# sch_Camera.net
KiCad netlist of a schematic drawn in Altium Designer
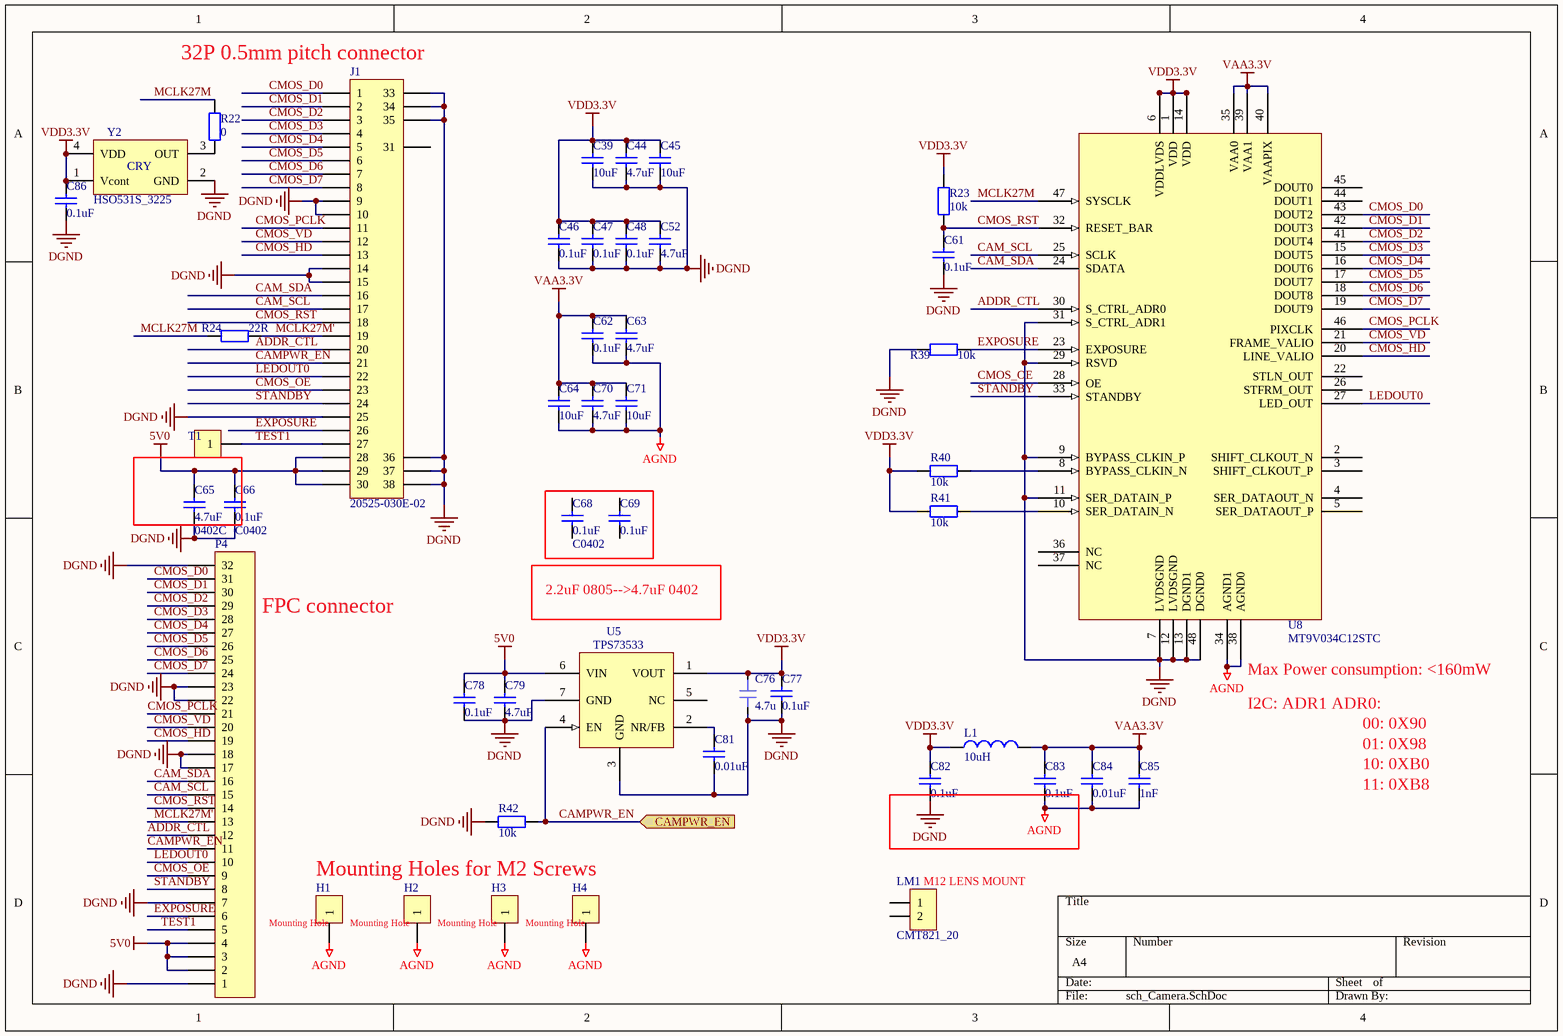
[diagram p0: sch_Camera.SchDoc]

(export (version "E")
  (design (tool "Eeschema 10.0.6"))
  (components
    (comp (ref "C39")
      (value "10uF")
      (footprint "0805C")
      (description "Capacitor")
      (fields (field (name "PUBLISHER") "Altium Limited"))
      (libsource (lib "Miscellaneous Devices") (part "Cap"))
    )
    (comp (ref "C44")
      (value "4.7uF")
      (footprint "0402C")
      (description "Capacitor")
      (fields (field (name "PUBLISHER") "Altium Limited"))
      (libsource (lib "Miscellaneous Devices") (part "Cap"))
    )
    (comp (ref "C45")
      (value "10uF")
      (footprint "0805C")
      (description "Capacitor")
      (fields (field (name "PUBLISHER") "Altium Limited"))
      (libsource (lib "Miscellaneous Devices") (part "Cap"))
    )
    (comp (ref "C46")
      (value "0.1uF")
      (footprint "0402C")
      (description "Capacitor")
      (fields (field (name "PUBLISHER") "Altium Limited"))
      (libsource (lib "Miscellaneous Devices") (part "Cap"))
    )
    (comp (ref "C47")
      (value "0.1uF")
      (footprint "0402C")
      (description "Capacitor")
      (fields (field (name "PUBLISHER") "Altium Limited"))
      (libsource (lib "Miscellaneous Devices") (part "Cap"))
    )
    (comp (ref "C48")
      (value "0.1uF")
      (footprint "0402C")
      (description "Capacitor")
      (fields (field (name "PUBLISHER") "Altium Limited"))
      (libsource (lib "Miscellaneous Devices") (part "Cap"))
    )
    (comp (ref "C52")
      (value "4.7uF")
      (footprint "0402C")
      (description "Capacitor")
      (fields (field (name "PUBLISHER") "Altium Limited"))
      (libsource (lib "Miscellaneous Devices") (part "Cap"))
    )
    (comp (ref "C61")
      (value "0.1uF")
      (footprint "0402C")
      (description "Capacitor")
      (fields (field (name "PUBLISHER") "Altium Limited"))
      (libsource (lib "Miscellaneous Devices") (part "Cap"))
    )
    (comp (ref "C62")
      (value "0.1uF")
      (footprint "0402C")
      (description "Capacitor")
      (fields (field (name "PUBLISHER") "Altium Limited"))
      (libsource (lib "Miscellaneous Devices") (part "Cap"))
    )
    (comp (ref "C63")
      (value "4.7uF")
      (footprint "0402C")
      (description "Capacitor")
      (fields (field (name "PUBLISHER") "Altium Limited"))
      (libsource (lib "Miscellaneous Devices") (part "Cap"))
    )
    (comp (ref "C64")
      (value "10uF")
      (footprint "0805C")
      (description "Capacitor")
      (fields (field (name "PUBLISHER") "Altium Limited"))
      (libsource (lib "Miscellaneous Devices") (part "Cap"))
    )
    (comp (ref "C65")
      (value "4.7uF")
      (footprint "0402C")
      (description "Capacitor")
      (fields (field (name "ALTIUM_VALUE") "0402C") (field (name "PUBLISHER") "Altium Limited"))
      (libsource (lib "Miscellaneous Devices") (part "Cap"))
    )
    (comp (ref "C66")
      (value "0.1uF")
      (footprint "0402C")
      (description "Capacitor")
      (fields (field (name "ALTIUM_VALUE") "C0402") (field (name "PUBLISHER") "Altium Limited"))
      (libsource (lib "Miscellaneous Devices") (part "Cap"))
    )
    (comp (ref "C68")
      (value "0.1uF")
      (footprint "0402C")
      (description "Capacitor")
      (fields (field (name "ALTIUM_VALUE") "C0402") (field (name "PUBLISHER") "Altium Limited"))
      (libsource (lib "Miscellaneous Devices") (part "Cap"))
    )
    (comp (ref "C69")
      (value "0.1uF")
      (footprint "0402C")
      (description "Capacitor")
      (fields (field (name "PUBLISHER") "Altium Limited"))
      (libsource (lib "Miscellaneous Devices") (part "Cap"))
    )
    (comp (ref "C70")
      (value "4.7uF")
      (footprint "0402C")
      (description "Capacitor")
      (fields (field (name "PUBLISHER") "Altium Limited"))
      (libsource (lib "Miscellaneous Devices") (part "Cap"))
    )
    (comp (ref "C71")
      (value "10uF")
      (footprint "0805C")
      (description "Capacitor")
      (fields (field (name "PUBLISHER") "Altium Limited"))
      (libsource (lib "Miscellaneous Devices") (part "Cap"))
    )
    (comp (ref "C76")
      (value "4.7u")
      (footprint "0402C_L")
      (description "CC0402MRX5R5BB475")
      (libsource (lib "V0P1") (part "cap0402"))
    )
    (comp (ref "C77")
      (value "0.1uF")
      (footprint "0402C_L")
      (description "Capacitor")
      (fields (field (name "PUBLISHER") "Altium Limited"))
      (libsource (lib "Miscellaneous Devices") (part "Cap"))
    )
    (comp (ref "C78")
      (value "0.1uF")
      (footprint "0402C")
      (description "Capacitor")
      (fields (field (name "PUBLISHER") "Altium Limited"))
      (libsource (lib "Miscellaneous Devices") (part "Cap"))
    )
    (comp (ref "C79")
      (value "4.7uF")
      (footprint "0402C_L")
      (description "Capacitor")
      (fields (field (name "PUBLISHER") "Altium Limited"))
      (libsource (lib "Miscellaneous Devices") (part "Cap"))
    )
    (comp (ref "C81")
      (value "0.01uF")
      (footprint "0402C_L")
      (description "Capacitor")
      (fields (field (name "PUBLISHER") "Altium Limited"))
      (libsource (lib "Miscellaneous Devices") (part "Cap"))
    )
    (comp (ref "C82")
      (value "0.1uF")
      (footprint "0402C_L")
      (description "Capacitor")
      (fields (field (name "PUBLISHER") "Altium Limited"))
      (libsource (lib "Miscellaneous Devices") (part "Cap"))
    )
    (comp (ref "C83")
      (value "0.1uF")
      (footprint "0402C_L")
      (description "Capacitor")
      (fields (field (name "PUBLISHER") "Altium Limited"))
      (libsource (lib "Miscellaneous Devices") (part "Cap"))
    )
    (comp (ref "C84")
      (value "0.01uF")
      (footprint "0402C_L")
      (description "Capacitor")
      (fields (field (name "PUBLISHER") "Altium Limited"))
      (libsource (lib "Miscellaneous Devices") (part "Cap"))
    )
    (comp (ref "C85")
      (value "1nF")
      (footprint "0402C_L")
      (description "Capacitor")
      (fields (field (name "PUBLISHER") "Altium Limited"))
      (libsource (lib "Miscellaneous Devices") (part "Cap"))
    )
    (comp (ref "C86")
      (value "0.1uF")
      (footprint "0402C")
      (description "Capacitor")
      (fields (field (name "PUBLISHER") "Altium Limited"))
      (libsource (lib "Miscellaneous Devices") (part "Cap"))
    )
    (comp (ref "H1")
      (value "CON1")
      (footprint "PAD_M3_D350_450")
      (description "Connector")
      (libsource (lib "") (part "CON1_1"))
    )
    (comp (ref "H2")
      (value "CON1")
      (footprint "PAD_M3_D350_450")
      (description "Connector")
      (libsource (lib "") (part "CON1_1"))
    )
    (comp (ref "H3")
      (value "CON1")
      (footprint "PAD_M3_D350_450")
      (description "Connector")
      (libsource (lib "") (part "CON1_1"))
    )
    (comp (ref "H4")
      (value "CON1")
      (footprint "PAD_M3_D350_450")
      (description "Connector")
      (libsource (lib "") (part "CON1_1"))
    )
    (comp (ref "J1")
      (value "20525-030E-02")
      (footprint "HSA30_P40L196W42H10_20525")
      (libsource (lib "SZG") (part "20525-030E-02"))
    )
    (comp (ref "L1")
      (value "10uH")
      (footprint "0805R")
      (description "Inductor")
      (libsource (lib "SWUST_ROBOT") (part "Inductor"))
    )
    (comp (ref "LM1")
      (value "CMT821_20")
      (footprint "PAD_M3_D350_450")
      (description "Connector")
      (libsource (lib "SuperSchLib") (part "CON2"))
    )
    (comp (ref "P4")
      (value "Header_32")
      (footprint "HS32A_FPC_P50L2350W480H210")
      (description "Header, 30-Pin, Dual row")
      (fields (field (name "PUBLISHER") "Altium Limited"))
      (libsource (lib "TXW") (part "Header 30X2"))
    )
    (comp (ref "R22")
      (value "0")
      (footprint "0402R")
      (description "Resistor")
      (fields (field (name "Comment") "0R") (field (name "PUBLISHER") "Altium Limited"))
      (libsource (lib "") (part "Resistor_2"))
    )
    (comp (ref "R23")
      (value "10k")
      (footprint "0402R")
      (description "Resistor")
      (fields (field (name "Comment") "10K") (field (name "PUBLISHER") "Altium Limited"))
      (libsource (lib "") (part "Resistor_1"))
    )
    (comp (ref "R24")
      (value "22R")
      (footprint "0402R")
      (description "Resistor")
      (fields (field (name "PUBLISHER") "Altium Limited"))
      (libsource (lib "") (part "Resistor_1"))
    )
    (comp (ref "R39")
      (value "10k")
      (footprint "0402R")
      (description "Resistor")
      (fields (field (name "Comment") "10K") (field (name "PUBLISHER") "Altium Limited"))
      (libsource (lib "SZG") (part "Resistor"))
    )
    (comp (ref "R40")
      (value "10k")
      (footprint "0402R")
      (description "Resistor")
      (fields (field (name "Comment") "10K") (field (name "PUBLISHER") "Altium Limited"))
      (libsource (lib "SZG") (part "Resistor"))
    )
    (comp (ref "R41")
      (value "10k")
      (footprint "0402R")
      (description "Resistor")
      (fields (field (name "Comment") "10K") (field (name "PUBLISHER") "Altium Limited"))
      (libsource (lib "SZG") (part "Resistor"))
    )
    (comp (ref "R42")
      (value "10k")
      (footprint "0402R_L")
      (description "Resistor")
      (fields (field (name "Comment") "10K") (field (name "PUBLISHER") "Altium Limited"))
      (libsource (lib "") (part "Resistor_3"))
    )
    (comp (ref "T1")
      (value "CON1")
      (footprint "PAD_TP_D1.2")
      (description "Connector")
      (libsource (lib "SuperSchLib") (part "CON1"))
    )
    (comp (ref "U5")
      (value "TPS73533")
      (footprint "SON6_P65L21W21H8_DRV")
      (libsource (lib "SZG") (part "TPS73533"))
    )
    (comp (ref "U8")
      (value "MT9V034C12STC")
      (footprint "CLCC48_P80L114W114H23")
      (libsource (lib "TXW") (part "MT9V034"))
    )
    (comp (ref "Y2")
      (value "HSO531S_3225")
      (footprint "XTAL_3225")
      (description "有源晶振")
      (libsource (lib "超集元件库") (part "CRY"))
    )
  )
  (nets
    (net (code "1") (name "/ADDR_CTL") (class "Default")
      (node (ref "J1") (pin "20") (pinfunction "20_20") (pintype "passive"))
      (node (ref "P4") (pin "12") (pinfunction "12_12") (pintype "passive"))
      (node (ref "U8") (pin "30") (pinfunction "S_CTRL_ADR0_30") (pintype "input"))
    )
    (net (code "2") (name "/CAMPWR_EN") (class "Default")
      (node (ref "J1") (pin "21") (pinfunction "21_21") (pintype "passive"))
      (node (ref "P4") (pin "11") (pinfunction "11_11") (pintype "passive"))
      (node (ref "R42") (pin "2") (pinfunction "2_2") (pintype "passive"))
      (node (ref "U5") (pin "4") (pinfunction "EN_4") (pintype "input"))
    )
    (net (code "3") (name "/CAM_SCL") (class "Default")
      (node (ref "J1") (pin "17") (pinfunction "17_17") (pintype "passive"))
      (node (ref "P4") (pin "15") (pinfunction "15_15") (pintype "passive"))
      (node (ref "U8") (pin "25") (pinfunction "SCLK_25") (pintype "input"))
    )
    (net (code "4") (name "/CAM_SDA") (class "Default")
      (node (ref "J1") (pin "16") (pinfunction "16_16") (pintype "passive"))
      (node (ref "P4") (pin "16") (pinfunction "16_16") (pintype "passive"))
      (node (ref "U8") (pin "24") (pinfunction "SDATA_24") (pintype "passive"))
    )
    (net (code "5") (name "/CMOS_D0") (class "Default")
      (node (ref "J1") (pin "1") (pinfunction "1_1") (pintype "passive"))
      (node (ref "P4") (pin "31") (pinfunction "31_31") (pintype "passive"))
      (node (ref "U8") (pin "43") (pinfunction "DOUT2_43") (pintype "passive"))
    )
    (net (code "6") (name "/CMOS_D1") (class "Default")
      (node (ref "J1") (pin "2") (pinfunction "2_2") (pintype "passive"))
      (node (ref "P4") (pin "30") (pinfunction "30_30") (pintype "passive"))
      (node (ref "U8") (pin "42") (pinfunction "DOUT3_42") (pintype "passive"))
    )
    (net (code "7") (name "/CMOS_D2") (class "Default")
      (node (ref "J1") (pin "3") (pinfunction "3_3") (pintype "passive"))
      (node (ref "P4") (pin "29") (pinfunction "29_29") (pintype "passive"))
      (node (ref "U8") (pin "41") (pinfunction "DOUT4_41") (pintype "passive"))
    )
    (net (code "8") (name "/CMOS_D3") (class "Default")
      (node (ref "J1") (pin "4") (pinfunction "4_4") (pintype "passive"))
      (node (ref "P4") (pin "28") (pinfunction "28_28") (pintype "passive"))
      (node (ref "U8") (pin "15") (pinfunction "DOUT5_15") (pintype "passive"))
    )
    (net (code "9") (name "/CMOS_D4") (class "Default")
      (node (ref "J1") (pin "5") (pinfunction "5_5") (pintype "passive"))
      (node (ref "P4") (pin "27") (pinfunction "27_27") (pintype "passive"))
      (node (ref "U8") (pin "16") (pinfunction "DOUT6_16") (pintype "passive"))
    )
    (net (code "10") (name "/CMOS_D5") (class "Default")
      (node (ref "J1") (pin "6") (pinfunction "6_6") (pintype "passive"))
      (node (ref "P4") (pin "26") (pinfunction "26_26") (pintype "passive"))
      (node (ref "U8") (pin "17") (pinfunction "DOUT7_17") (pintype "passive"))
    )
    (net (code "11") (name "/CMOS_D6") (class "Default")
      (node (ref "J1") (pin "7") (pinfunction "7_7") (pintype "passive"))
      (node (ref "P4") (pin "25") (pinfunction "25_25") (pintype "passive"))
      (node (ref "U8") (pin "18") (pinfunction "DOUT8_18") (pintype "passive"))
    )
    (net (code "12") (name "/CMOS_D7") (class "Default")
      (node (ref "J1") (pin "8") (pinfunction "8_8") (pintype "passive"))
      (node (ref "P4") (pin "24") (pinfunction "24_24") (pintype "passive"))
      (node (ref "U8") (pin "19") (pinfunction "DOUT9_19") (pintype "passive"))
    )
    (net (code "13") (name "/CMOS_HD") (class "Default")
      (node (ref "J1") (pin "13") (pinfunction "13_13") (pintype "passive"))
      (node (ref "P4") (pin "19") (pinfunction "19_19") (pintype "passive"))
      (node (ref "U8") (pin "20") (pinfunction "LINE_VALIO_20") (pintype "passive"))
    )
    (net (code "14") (name "/CMOS_OE") (class "Default")
      (node (ref "J1") (pin "23") (pinfunction "23_23") (pintype "passive"))
      (node (ref "P4") (pin "9") (pinfunction "9_9") (pintype "passive"))
      (node (ref "U8") (pin "28") (pinfunction "OE_28") (pintype "input"))
    )
    (net (code "15") (name "/CMOS_PCLK") (class "Default")
      (node (ref "J1") (pin "11") (pinfunction "11_11") (pintype "passive"))
      (node (ref "P4") (pin "21") (pinfunction "21_21") (pintype "passive"))
      (node (ref "U8") (pin "46") (pinfunction "PIXCLK_46") (pintype "passive"))
    )
    (net (code "16") (name "/CMOS_RST") (class "Default")
      (node (ref "C61") (pin "2") (pinfunction "2_2") (pintype "passive"))
      (node (ref "J1") (pin "18") (pinfunction "18_18") (pintype "passive"))
      (node (ref "P4") (pin "14") (pinfunction "14_14") (pintype "passive"))
      (node (ref "R23") (pin "1") (pinfunction "1_1") (pintype "passive"))
      (node (ref "U8") (pin "32") (pinfunction "RESET_BAR_32") (pintype "input"))
    )
    (net (code "17") (name "/CMOS_VD") (class "Default")
      (node (ref "J1") (pin "12") (pinfunction "12_12") (pintype "passive"))
      (node (ref "P4") (pin "20") (pinfunction "20_20") (pintype "passive"))
      (node (ref "U8") (pin "21") (pinfunction "FRAME_VALIO_21") (pintype "passive"))
    )
    (net (code "18") (name "/EXPOSURE") (class "Default")
      (node (ref "J1") (pin "26") (pinfunction "26_26") (pintype "passive"))
      (node (ref "P4") (pin "6") (pinfunction "6_6") (pintype "passive"))
      (node (ref "R39") (pin "1") (pinfunction "1_1") (pintype "passive"))
      (node (ref "U8") (pin "23") (pinfunction "EXPOSURE_23") (pintype "input"))
    )
    (net (code "19") (name "/LEDOUT0") (class "Default")
      (node (ref "J1") (pin "22") (pinfunction "22_22") (pintype "passive"))
      (node (ref "P4") (pin "10") (pinfunction "10_10") (pintype "passive"))
      (node (ref "U8") (pin "27") (pinfunction "LED_OUT_27") (pintype "passive"))
    )
    (net (code "20") (name "/MCLK27M") (class "Default")
      (node (ref "R22") (pin "1") (pinfunction "1_1") (pintype "passive"))
      (node (ref "R24") (pin "1") (pinfunction "1_1") (pintype "passive"))
      (node (ref "U8") (pin "47") (pinfunction "SYSCLK_47") (pintype "input"))
    )
    (net (code "21") (name "/MCLK27M'") (class "Default")
      (node (ref "J1") (pin "19") (pinfunction "19_19") (pintype "passive"))
      (node (ref "P4") (pin "13") (pinfunction "13_13") (pintype "passive"))
      (node (ref "R24") (pin "2") (pinfunction "2_2") (pintype "passive"))
    )
    (net (code "22") (name "/STANDBY") (class "Default")
      (node (ref "J1") (pin "24") (pinfunction "24_24") (pintype "passive"))
      (node (ref "P4") (pin "8") (pinfunction "8_8") (pintype "passive"))
      (node (ref "U8") (pin "33") (pinfunction "STANDBY_33") (pintype "input"))
    )
    (net (code "23") (name "/TEST1") (class "Default")
      (node (ref "J1") (pin "27") (pinfunction "27_27") (pintype "passive"))
      (node (ref "P4") (pin "5") (pinfunction "5_5") (pintype "passive"))
      (node (ref "T1") (pin "1") (pinfunction "1_1") (pintype "passive"))
    )
    (net (code "24") (name "5V0") (class "Default")
      (node (ref "C65") (pin "2") (pinfunction "2_2") (pintype "passive"))
      (node (ref "C66") (pin "2") (pinfunction "2_2") (pintype "passive"))
      (node (ref "C78") (pin "2") (pinfunction "2_2") (pintype "passive"))
      (node (ref "C79") (pin "2") (pinfunction "2_2") (pintype "passive"))
      (node (ref "J1") (pin "28") (pinfunction "28_28") (pintype "passive"))
      (node (ref "J1") (pin "29") (pinfunction "29_29") (pintype "passive"))
      (node (ref "J1") (pin "30") (pinfunction "30_30") (pintype "passive"))
      (node (ref "P4") (pin "2") (pinfunction "2_2") (pintype "passive"))
      (node (ref "P4") (pin "3") (pinfunction "3_3") (pintype "passive"))
      (node (ref "P4") (pin "4") (pinfunction "4_4") (pintype "passive"))
      (node (ref "U5") (pin "6") (pinfunction "VIN_6") (pintype "passive"))
    )
    (net (code "25") (name "AGND") (class "Default")
      (node (ref "C62") (pin "1") (pinfunction "1_1") (pintype "passive"))
      (node (ref "C63") (pin "1") (pinfunction "1_1") (pintype "passive"))
      (node (ref "C64") (pin "1") (pinfunction "1_1") (pintype "passive"))
      (node (ref "C70") (pin "1") (pinfunction "1_1") (pintype "passive"))
      (node (ref "C71") (pin "1") (pinfunction "1_1") (pintype "passive"))
      (node (ref "C83") (pin "1") (pinfunction "1_1") (pintype "passive"))
      (node (ref "C84") (pin "1") (pinfunction "1_1") (pintype "passive"))
      (node (ref "C85") (pin "1") (pinfunction "1_1") (pintype "passive"))
      (node (ref "H1") (pin "1") (pinfunction "1_1") (pintype "passive"))
      (node (ref "H2") (pin "1") (pinfunction "1_1") (pintype "passive"))
      (node (ref "H3") (pin "1") (pinfunction "1_1") (pintype "passive"))
      (node (ref "H4") (pin "1") (pinfunction "1_1") (pintype "passive"))
      (node (ref "U8") (pin "34") (pinfunction "AGND1_34") (pintype "power_in"))
      (node (ref "U8") (pin "38") (pinfunction "AGND0_38") (pintype "power_in"))
    )
    (net (code "26") (name "DGND") (class "Default")
      (node (ref "C39") (pin "1") (pinfunction "1_1") (pintype "passive"))
      (node (ref "C44") (pin "1") (pinfunction "1_1") (pintype "passive"))
      (node (ref "C45") (pin "1") (pinfunction "1_1") (pintype "passive"))
      (node (ref "C46") (pin "1") (pinfunction "1_1") (pintype "passive"))
      (node (ref "C47") (pin "1") (pinfunction "1_1") (pintype "passive"))
      (node (ref "C48") (pin "1") (pinfunction "1_1") (pintype "passive"))
      (node (ref "C52") (pin "1") (pinfunction "1_1") (pintype "passive"))
      (node (ref "C61") (pin "1") (pinfunction "1_1") (pintype "passive"))
      (node (ref "C65") (pin "1") (pinfunction "1_1") (pintype "passive"))
      (node (ref "C66") (pin "1") (pinfunction "1_1") (pintype "passive"))
      (node (ref "C76") (pin "2") (pinfunction "2_2") (pintype "passive"))
      (node (ref "C77") (pin "1") (pinfunction "1_1") (pintype "passive"))
      (node (ref "C78") (pin "1") (pinfunction "1_1") (pintype "passive"))
      (node (ref "C79") (pin "1") (pinfunction "1_1") (pintype "passive"))
      (node (ref "C81") (pin "1") (pinfunction "1_1") (pintype "passive"))
      (node (ref "C82") (pin "1") (pinfunction "1_1") (pintype "passive"))
      (node (ref "C86") (pin "1") (pinfunction "1_1") (pintype "passive"))
      (node (ref "J1") (pin "10") (pinfunction "10_10") (pintype "passive"))
      (node (ref "J1") (pin "14") (pinfunction "14_14") (pintype "passive"))
      (node (ref "J1") (pin "15") (pinfunction "15_15") (pintype "passive"))
      (node (ref "J1") (pin "25") (pinfunction "25_25") (pintype "passive"))
      (node (ref "J1") (pin "33") (pinfunction "33_33") (pintype "passive"))
      (node (ref "J1") (pin "34") (pinfunction "34_34") (pintype "passive"))
      (node (ref "J1") (pin "35") (pinfunction "35_35") (pintype "passive"))
      (node (ref "J1") (pin "36") (pinfunction "36_36") (pintype "passive"))
      (node (ref "J1") (pin "37") (pinfunction "37_37") (pintype "passive"))
      (node (ref "J1") (pin "38") (pinfunction "38_38") (pintype "passive"))
      (node (ref "J1") (pin "9") (pinfunction "9_9") (pintype "passive"))
      (node (ref "P4") (pin "1") (pinfunction "1_1") (pintype "passive"))
      (node (ref "P4") (pin "17") (pinfunction "17_17") (pintype "passive"))
      (node (ref "P4") (pin "18") (pinfunction "18_18") (pintype "passive"))
      (node (ref "P4") (pin "22") (pinfunction "22_22") (pintype "passive"))
      (node (ref "P4") (pin "23") (pinfunction "23_23") (pintype "passive"))
      (node (ref "P4") (pin "32") (pinfunction "32_32") (pintype "passive"))
      (node (ref "P4") (pin "7") (pinfunction "7_7") (pintype "passive"))
      (node (ref "R39") (pin "2") (pinfunction "2_2") (pintype "passive"))
      (node (ref "R42") (pin "1") (pinfunction "1_1") (pintype "passive"))
      (node (ref "U5") (pin "3") (pinfunction "GND_3") (pintype "passive"))
      (node (ref "U5") (pin "7") (pinfunction "GND_7") (pintype "passive"))
      (node (ref "U8") (pin "11") (pinfunction "SER_DATAIN_P_11") (pintype "input"))
      (node (ref "U8") (pin "12") (pinfunction "LVDSGND_12") (pintype "power_in"))
      (node (ref "U8") (pin "13") (pinfunction "DGND1_13") (pintype "power_in"))
      (node (ref "U8") (pin "29") (pinfunction "RSVD_29") (pintype "input"))
      (node (ref "U8") (pin "31") (pinfunction "S_CTRL_ADR1_31") (pintype "input"))
      (node (ref "U8") (pin "48") (pinfunction "DGND0_48") (pintype "power_in"))
      (node (ref "U8") (pin "7") (pinfunction "LVDSGND_7") (pintype "power_in"))
      (node (ref "U8") (pin "9") (pinfunction "BYPASS_CLKIN_P_9") (pintype "input"))
      (node (ref "Y2") (pin "2") (pinfunction "GND_2") (pintype "passive"))
    )
    (net (code "27") (name "Net-(U5-NR{slash}FB)") (class "Default")
      (node (ref "C81") (pin "2") (pinfunction "2_2") (pintype "passive"))
      (node (ref "U5") (pin "2") (pinfunction "NR/FB_2") (pintype "passive"))
    )
    (net (code "28") (name "Net-(U8-BYPASS_CLKIN_N)") (class "Default")
      (node (ref "R40") (pin "1") (pinfunction "1_1") (pintype "passive"))
      (node (ref "U8") (pin "8") (pinfunction "BYPASS_CLKIN_N_8") (pintype "input"))
    )
    (net (code "29") (name "Net-(U8-SER_DATAIN_N)") (class "Default")
      (node (ref "R41") (pin "1") (pinfunction "1_1") (pintype "passive"))
      (node (ref "U8") (pin "10") (pinfunction "SER_DATAIN_N_10") (pintype "input"))
    )
    (net (code "30") (name "Net-(Y2-OUT)") (class "Default")
      (node (ref "R22") (pin "2") (pinfunction "2_2") (pintype "passive"))
      (node (ref "Y2") (pin "3") (pinfunction "OUT_3") (pintype "passive"))
    )
    (net (code "31") (name "VAA3.3V") (class "Default")
      (node (ref "C62") (pin "2") (pinfunction "2_2") (pintype "passive"))
      (node (ref "C63") (pin "2") (pinfunction "2_2") (pintype "passive"))
      (node (ref "C64") (pin "2") (pinfunction "2_2") (pintype "passive"))
      (node (ref "C70") (pin "2") (pinfunction "2_2") (pintype "passive"))
      (node (ref "C71") (pin "2") (pinfunction "2_2") (pintype "passive"))
      (node (ref "C83") (pin "2") (pinfunction "2_2") (pintype "passive"))
      (node (ref "C84") (pin "2") (pinfunction "2_2") (pintype "passive"))
      (node (ref "C85") (pin "2") (pinfunction "2_2") (pintype "passive"))
      (node (ref "L1") (pin "2") (pinfunction "2_2") (pintype "passive"))
      (node (ref "U8") (pin "35") (pinfunction "VAA0_35") (pintype "power_in"))
      (node (ref "U8") (pin "39") (pinfunction "VAA1_39") (pintype "power_in"))
      (node (ref "U8") (pin "40") (pinfunction "VAAPIX_40") (pintype "power_in"))
    )
    (net (code "32") (name "VDD3.3V") (class "Default")
      (node (ref "C39") (pin "2") (pinfunction "2_2") (pintype "passive"))
      (node (ref "C44") (pin "2") (pinfunction "2_2") (pintype "passive"))
      (node (ref "C45") (pin "2") (pinfunction "2_2") (pintype "passive"))
      (node (ref "C46") (pin "2") (pinfunction "2_2") (pintype "passive"))
      (node (ref "C47") (pin "2") (pinfunction "2_2") (pintype "passive"))
      (node (ref "C48") (pin "2") (pinfunction "2_2") (pintype "passive"))
      (node (ref "C52") (pin "2") (pinfunction "2_2") (pintype "passive"))
      (node (ref "C76") (pin "1") (pinfunction "1_1") (pintype "passive"))
      (node (ref "C77") (pin "2") (pinfunction "2_2") (pintype "passive"))
      (node (ref "C82") (pin "2") (pinfunction "2_2") (pintype "passive"))
      (node (ref "C86") (pin "2") (pinfunction "2_2") (pintype "passive"))
      (node (ref "L1") (pin "1") (pinfunction "1_1") (pintype "passive"))
      (node (ref "R23") (pin "2") (pinfunction "2_2") (pintype "passive"))
      (node (ref "R40") (pin "2") (pinfunction "2_2") (pintype "passive"))
      (node (ref "R41") (pin "2") (pinfunction "2_2") (pintype "passive"))
      (node (ref "U5") (pin "1") (pinfunction "VOUT_1") (pintype "passive"))
      (node (ref "U8") (pin "1") (pinfunction "VDD_1") (pintype "power_in"))
      (node (ref "U8") (pin "14") (pinfunction "VDD_14") (pintype "power_in"))
      (node (ref "U8") (pin "6") (pinfunction "VDDLVDS_6") (pintype "power_in"))
      (node (ref "Y2") (pin "1") (pinfunction "Vcont_1") (pintype "passive"))
      (node (ref "Y2") (pin "4") (pinfunction "VDD_4") (pintype "passive"))
    )
    (net (code "33") (name "unconnected-(C68-Pad1)") (class "Default")
      (node (ref "C68") (pin "1") (pinfunction "1_1") (pintype "passive"))
    )
    (net (code "34") (name "unconnected-(C68-Pad2)") (class "Default")
      (node (ref "C68") (pin "2") (pinfunction "2_2") (pintype "passive"))
    )
    (net (code "35") (name "unconnected-(C69-Pad1)") (class "Default")
      (node (ref "C69") (pin "1") (pinfunction "1_1") (pintype "passive"))
    )
    (net (code "36") (name "unconnected-(C69-Pad2)") (class "Default")
      (node (ref "C69") (pin "2") (pinfunction "2_2") (pintype "passive"))
    )
    (net (code "37") (name "unconnected-(J1-Pad31)") (class "Default")
      (node (ref "J1") (pin "31") (pinfunction "31_31") (pintype "passive"))
    )
    (net (code "38") (name "unconnected-(LM1-Pad1)") (class "Default")
      (node (ref "LM1") (pin "1") (pinfunction "1_1") (pintype "passive"))
    )
    (net (code "39") (name "unconnected-(LM1-Pad2)") (class "Default")
      (node (ref "LM1") (pin "2") (pinfunction "2_2") (pintype "passive"))
    )
    (net (code "40") (name "unconnected-(U5-NC-Pad5)") (class "Default")
      (node (ref "U5") (pin "5") (pinfunction "NC_5") (pintype "passive"))
    )
    (net (code "41") (name "unconnected-(U8-DOUT0-Pad45)") (class "Default")
      (node (ref "U8") (pin "45") (pinfunction "DOUT0_45") (pintype "passive"))
    )
    (net (code "42") (name "unconnected-(U8-DOUT1-Pad44)") (class "Default")
      (node (ref "U8") (pin "44") (pinfunction "DOUT1_44") (pintype "passive"))
    )
    (net (code "43") (name "unconnected-(U8-NC-Pad36)") (class "Default")
      (node (ref "U8") (pin "36") (pinfunction "NC_36") (pintype "passive"))
    )
    (net (code "44") (name "unconnected-(U8-NC-Pad37)") (class "Default")
      (node (ref "U8") (pin "37") (pinfunction "NC_37") (pintype "power_in"))
    )
    (net (code "45") (name "unconnected-(U8-SER_DATAOUT_N-Pad4)") (class "Default")
      (node (ref "U8") (pin "4") (pinfunction "SER_DATAOUT_N_4") (pintype "passive"))
    )
    (net (code "46") (name "unconnected-(U8-SER_DATAOUT_P-Pad5)") (class "Default")
      (node (ref "U8") (pin "5") (pinfunction "SER_DATAOUT_P_5") (pintype "passive"))
    )
    (net (code "47") (name "unconnected-(U8-SHIFT_CLKOUT_N-Pad2)") (class "Default")
      (node (ref "U8") (pin "2") (pinfunction "SHIFT_CLKOUT_N_2") (pintype "passive"))
    )
    (net (code "48") (name "unconnected-(U8-SHIFT_CLKOUT_P-Pad3)") (class "Default")
      (node (ref "U8") (pin "3") (pinfunction "SHIFT_CLKOUT_P_3") (pintype "passive"))
    )
    (net (code "49") (name "unconnected-(U8-STFRM_OUT-Pad26)") (class "Default")
      (node (ref "U8") (pin "26") (pinfunction "STFRM_OUT_26") (pintype "passive"))
    )
    (net (code "50") (name "unconnected-(U8-STLN_OUT-Pad22)") (class "Default")
      (node (ref "U8") (pin "22") (pinfunction "STLN_OUT_22") (pintype "passive"))
    )
  )
)
